# ProPrj_Line_follow_3_2025-06-26.net
KiCad netlist of a schematic drawn in EasyEDA Pro
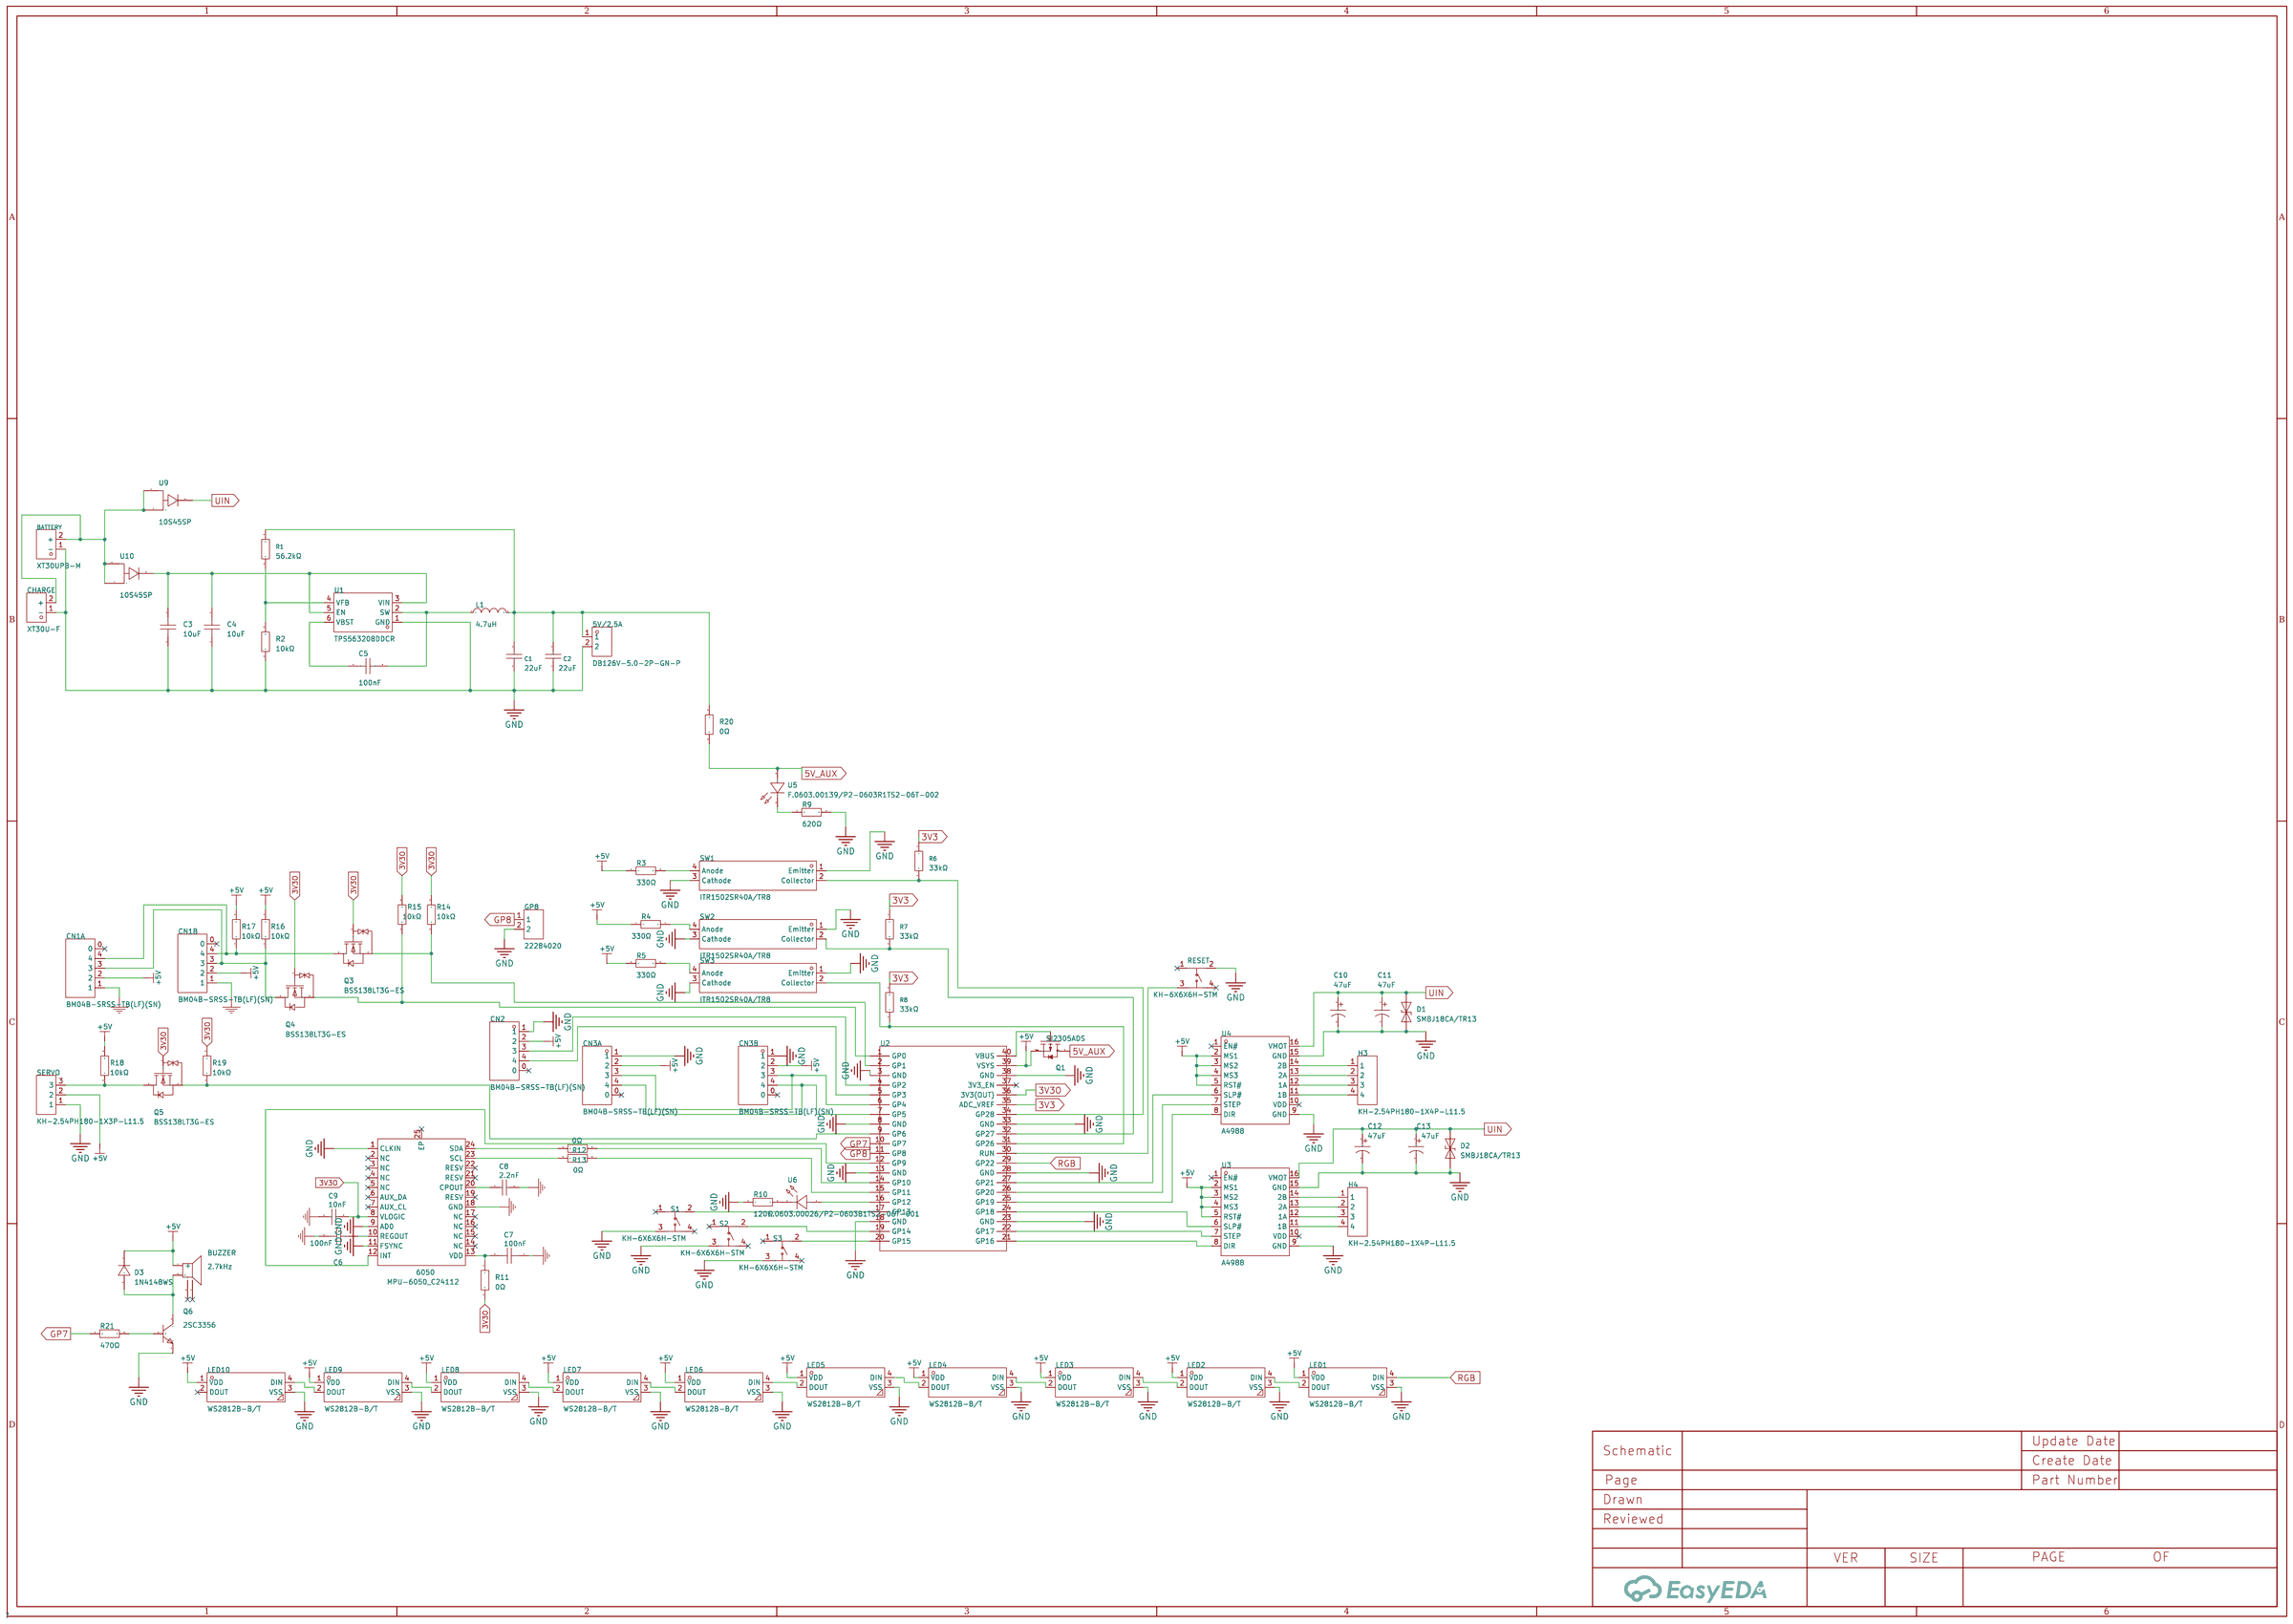
[diagram p0: schematic sheet]

(export (version "E")
  (design (tool "Eeschema 10.0.6"))
  (components
    (comp (ref "5V/2.5A")
      (value "DB126V-5.0-2P-GN-P")
      (footprint "easyedapro:CONN-TH_2P-P5.00_L7.8-W10.0")
      (fields (field (name "Manufacturer") "DORABO(地博电气)"))
      (libsource (lib "easyedapro") (part "DB126V-5.0-2P"))
    )
    (comp (ref "6050")
      (value "MPU-6050_C24112")
      (footprint "easyedapro:QFN-24_L4.0-W4.0-P0.50-BL-EP2.7")
      (fields
        (field (name "Manufacturer Part") "MPU-6050")
        (field (name "Manufacturer") "TDK InvenSense(应美盛)")
      )
      (libsource (lib "easyedapro") (part "MPU-6050_C24112"))
    )
    (comp (ref "BATTERY")
      (value "XT30UPB-M")
      (footprint "easyedapro:CONN-TH_XT30UPB-M")
      (fields (field (name "Manufacturer") "AMASS(艾迈斯)"))
      (libsource (lib "easyedapro") (part "XT30UPB-M"))
    )
    (comp (ref "BUZZER")
      (value "2.7kHz")
      (footprint "easyedapro:BUZ-SMD_4P-L8.5-W8.5-P8.50-BR")
      (fields (field (name "Manufacturer Part") "MLT-8530") (field (name "Manufacturer") "华能"))
      (libsource (lib "easyedapro") (part "MLT-8530"))
    )
    (comp (ref "C1")
      (value "22uF")
      (footprint "easyedapro:C1210")
      (fields
        (field (name "Manufacturer Part") "GRM32ER61E226KE15L")
        (field (name "Manufacturer") "muRata(村田)")
      )
      (libsource (lib "easyedapro") (part "GRM32ER61E226KE15L"))
    )
    (comp (ref "C2")
      (value "22uF")
      (footprint "easyedapro:C1210")
      (fields
        (field (name "Manufacturer Part") "GRM32ER61E226KE15L")
        (field (name "Manufacturer") "muRata(村田)")
      )
      (libsource (lib "easyedapro") (part "GRM32ER61E226KE15L"))
    )
    (comp (ref "C3")
      (value "10uF")
      (footprint "easyedapro:C1206")
      (fields
        (field (name "Manufacturer Part") "GRM31CR61E106KA12L")
        (field (name "Manufacturer") "muRata(村田)")
      )
      (libsource (lib "easyedapro") (part "GRM31CR61E106KA12L"))
    )
    (comp (ref "C4")
      (value "10uF")
      (footprint "easyedapro:C1206")
      (fields
        (field (name "Manufacturer Part") "GRM31CR61E106KA12L")
        (field (name "Manufacturer") "muRata(村田)")
      )
      (libsource (lib "easyedapro") (part "GRM31CR61E106KA12L"))
    )
    (comp (ref "C5")
      (value "100nF")
      (footprint "easyedapro:C0603")
      (fields
        (field (name "Manufacturer Part") "GRM188R71H104KA93D")
        (field (name "Manufacturer") "muRata(村田)")
      )
      (libsource (lib "easyedapro") (part "GRM188R71H104KA93D"))
    )
    (comp (ref "C6")
      (value "100nF")
      (footprint "easyedapro:C0603")
      (fields
        (field (name "Manufacturer Part") "CL10B104KB8NNNC")
        (field (name "Manufacturer") "SAMSUNG(三星)")
      )
      (libsource (lib "easyedapro") (part "100nF"))
    )
    (comp (ref "C7")
      (value "100nF")
      (footprint "easyedapro:C0603")
      (fields
        (field (name "Manufacturer Part") "CL10B104KB8NNNC")
        (field (name "Manufacturer") "SAMSUNG(三星)")
      )
      (libsource (lib "easyedapro") (part "100nF"))
    )
    (comp (ref "C8")
      (value "2.2nF")
      (footprint "easyedapro:C0603")
      (fields (field (name "Manufacturer Part") "0603B222K500NT") (field (name "Manufacturer") "FH(风华)"))
      (libsource (lib "easyedapro") (part "2.2nF"))
    )
    (comp (ref "C9")
      (value "10nF")
      (footprint "easyedapro:C0603")
      (fields
        (field (name "Manufacturer Part") "CL10B103KB8NNNC")
        (field (name "Manufacturer") "SAMSUNG(三星)")
      )
      (libsource (lib "easyedapro") (part "10nF"))
    )
    (comp (ref "C10")
      (value "47uF")
      (footprint "easyedapro:CAP-TH_BD6.3-P2.50-D1.0-FD")
      (fields
        (field (name "Manufacturer Part") "SPZ1HM470E08O00RAXXX")
        (field (name "Manufacturer") "AISHI(艾华集团)")
      )
      (libsource (lib "easyedapro") (part "SPZ1HM470E08000R"))
    )
    (comp (ref "C11")
      (value "47uF")
      (footprint "easyedapro:CAP-TH_BD6.3-P2.50-D1.0-FD")
      (fields
        (field (name "Manufacturer Part") "SPZ1HM470E08O00RAXXX")
        (field (name "Manufacturer") "AISHI(艾华集团)")
      )
      (libsource (lib "easyedapro") (part "SPZ1HM470E08000R"))
    )
    (comp (ref "C12")
      (value "47uF")
      (footprint "easyedapro:CAP-TH_BD6.3-P2.50-D1.0-FD")
      (fields
        (field (name "Manufacturer Part") "SPZ1HM470E08O00RAXXX")
        (field (name "Manufacturer") "AISHI(艾华集团)")
      )
      (libsource (lib "easyedapro") (part "SPZ1HM470E08000R"))
    )
    (comp (ref "C13")
      (value "47uF")
      (footprint "easyedapro:CAP-TH_BD6.3-P2.50-D1.0-FD")
      (fields
        (field (name "Manufacturer Part") "SPZ1HM470E08O00RAXXX")
        (field (name "Manufacturer") "AISHI(艾华集团)")
      )
      (libsource (lib "easyedapro") (part "SPZ1HM470E08000R"))
    )
    (comp (ref "CHARGE")
      (value "XT30U-F")
      (footprint "easyedapro:CONN-TH_XT30U-F")
      (fields (field (name "Manufacturer") "AMASS(艾迈斯)"))
      (libsource (lib "easyedapro") (part "XT30U-F"))
    )
    (comp (ref "CN1A")
      (value "BM04B-SRSS-TB(LF)(SN)")
      (footprint "easyedapro:CONN-SMD_BM04B-SRSS-TB")
      (fields (field (name "Manufacturer") "JST"))
      (libsource (lib "") (part "BM04B-SRSS-TB(LF)(SN)_1"))
    )
    (comp (ref "CN1B")
      (value "BM04B-SRSS-TB(LF)(SN)")
      (footprint "easyedapro:CONN-SMD_BM04B-SRSS-TB")
      (fields (field (name "Manufacturer") "JST"))
      (libsource (lib "") (part "BM04B-SRSS-TB(LF)(SN)_1"))
    )
    (comp (ref "CN2")
      (value "BM04B-SRSS-TB(LF)(SN)")
      (footprint "easyedapro:CONN-SMD_BM04B-SRSS-TB")
      (fields (field (name "Manufacturer") "JST"))
      (libsource (lib "easyedapro") (part "BM04B-SRSS-TB(LF)(SN)"))
    )
    (comp (ref "CN3A")
      (value "BM04B-SRSS-TB(LF)(SN)")
      (footprint "easyedapro:CONN-SMD_BM04B-SRSS-TB")
      (fields (field (name "Manufacturer") "JST"))
      (libsource (lib "easyedapro") (part "BM04B-SRSS-TB(LF)(SN)"))
    )
    (comp (ref "CN3B")
      (value "BM04B-SRSS-TB(LF)(SN)")
      (footprint "easyedapro:CONN-SMD_BM04B-SRSS-TB")
      (fields (field (name "Manufacturer") "JST"))
      (libsource (lib "easyedapro") (part "BM04B-SRSS-TB(LF)(SN)"))
    )
    (comp (ref "D1")
      (value "SMBJ18CA/TR13")
      (footprint "easyedapro:SMB_L4.6-W3.6-LS5.3-BI")
      (fields (field (name "Manufacturer") "Brightking(君耀电子)"))
      (libsource (lib "easyedapro") (part "SMBJ18CA-C78413"))
    )
    (comp (ref "D2")
      (value "SMBJ18CA/TR13")
      (footprint "easyedapro:SMB_L4.6-W3.6-LS5.3-BI")
      (fields (field (name "Manufacturer") "Brightking(君耀电子)"))
      (libsource (lib "easyedapro") (part "SMBJ18CA-C78413"))
    )
    (comp (ref "D3")
      (value "1N4148WS")
      (footprint "easyedapro:SOD-323_L1.8-W1.3-LS2.5-RD")
      (fields (field (name "Manufacturer") "CJ(江苏长电/长晶)"))
      (libsource (lib "easyedapro") (part "1N4148WS T4"))
    )
    (comp (ref "GP8")
      (value "22284020")
      (footprint "easyedapro:HDR-TH_2P-P2.54-V-M-1")
      (fields (field (name "Manufacturer") "MOLEX"))
      (libsource (lib "easyedapro") (part "22-28-4020"))
    )
    (comp (ref "H3")
      (value "KH-2.54PH180-1X4P-L11.5")
      (footprint "easyedapro:HDR-TH_4P-P2.54-V-M")
      (fields (field (name "Manufacturer") "kinghelm(金航标)"))
      (libsource (lib "easyedapro") (part "KH-2.54PH180-1X4P-L11.5"))
    )
    (comp (ref "H4")
      (value "KH-2.54PH180-1X4P-L11.5")
      (footprint "easyedapro:HDR-TH_4P-P2.54-V-M")
      (fields (field (name "Manufacturer") "kinghelm(金航标)"))
      (libsource (lib "easyedapro") (part "KH-2.54PH180-1X4P-L11.5"))
    )
    (comp (ref "L1")
      (value "4.7uH")
      (footprint "easyedapro:IND-SMD_L7.0-W6.6")
      (fields (field (name "Manufacturer Part") "FXL0630-4R7-M") (field (name "Manufacturer") "cjiang(长江微电)"))
      (libsource (lib "easyedapro") (part "FXL0630-4R7-M"))
    )
    (comp (ref "LED1")
      (value "WS2812B-B/T")
      (footprint "easyedapro:LED-SMD_4P-L5.0-W5.0-TL_WS2812B-B")
      (fields (field (name "Manufacturer") "worldsemi"))
      (libsource (lib "easyedapro") (part "WS2812B-B/W"))
    )
    (comp (ref "LED2")
      (value "WS2812B-B/T")
      (footprint "easyedapro:LED-SMD_4P-L5.0-W5.0-TL_WS2812B-B")
      (fields (field (name "Manufacturer") "worldsemi"))
      (libsource (lib "easyedapro") (part "WS2812B-B/W"))
    )
    (comp (ref "LED3")
      (value "WS2812B-B/T")
      (footprint "easyedapro:LED-SMD_4P-L5.0-W5.0-TL_WS2812B-B")
      (fields (field (name "Manufacturer") "worldsemi"))
      (libsource (lib "easyedapro") (part "WS2812B-B/W"))
    )
    (comp (ref "LED4")
      (value "WS2812B-B/T")
      (footprint "easyedapro:LED-SMD_4P-L5.0-W5.0-TL_WS2812B-B")
      (fields (field (name "Manufacturer") "worldsemi"))
      (libsource (lib "easyedapro") (part "WS2812B-B/W"))
    )
    (comp (ref "LED5")
      (value "WS2812B-B/T")
      (footprint "easyedapro:LED-SMD_4P-L5.0-W5.0-TL_WS2812B-B")
      (fields (field (name "Manufacturer") "worldsemi"))
      (libsource (lib "easyedapro") (part "WS2812B-B/W"))
    )
    (comp (ref "LED6")
      (value "WS2812B-B/T")
      (footprint "easyedapro:LED-SMD_4P-L5.0-W5.0-TL_WS2812B-B")
      (fields (field (name "Manufacturer") "worldsemi"))
      (libsource (lib "easyedapro") (part "WS2812B-B/W"))
    )
    (comp (ref "LED7")
      (value "WS2812B-B/T")
      (footprint "easyedapro:LED-SMD_4P-L5.0-W5.0-TL_WS2812B-B")
      (fields (field (name "Manufacturer") "worldsemi"))
      (libsource (lib "easyedapro") (part "WS2812B-B/W"))
    )
    (comp (ref "LED8")
      (value "WS2812B-B/T")
      (footprint "easyedapro:LED-SMD_4P-L5.0-W5.0-TL_WS2812B-B")
      (fields (field (name "Manufacturer") "worldsemi"))
      (libsource (lib "easyedapro") (part "WS2812B-B/W"))
    )
    (comp (ref "LED9")
      (value "WS2812B-B/T")
      (footprint "easyedapro:LED-SMD_4P-L5.0-W5.0-TL_WS2812B-B")
      (fields (field (name "Manufacturer") "worldsemi"))
      (libsource (lib "easyedapro") (part "WS2812B-B/W"))
    )
    (comp (ref "LED10")
      (value "WS2812B-B/T")
      (footprint "easyedapro:LED-SMD_4P-L5.0-W5.0-TL_WS2812B-B")
      (fields (field (name "Manufacturer") "worldsemi"))
      (libsource (lib "easyedapro") (part "WS2812B-B/W"))
    )
    (comp (ref "Q1")
      (value "SI2305ADS")
      (footprint "easyedapro:SOT-23-3_L2.9-W1.3-P1.90-LS2.4-BR")
      (fields (field (name "Manufacturer") "TECH PUBLIC(台舟)"))
      (libsource (lib "easyedapro") (part "SI2305ADS"))
    )
    (comp (ref "Q3")
      (value "BSS138LT3G-ES")
      (footprint "easyedapro:SOT-23-3_L2.9-W1.3-P1.90-LS2.4-BR")
      (fields (field (name "Manufacturer") "ElecSuper(静芯微)"))
      (libsource (lib "easyedapro") (part "BSS138LT3G-ES"))
    )
    (comp (ref "Q4")
      (value "BSS138LT3G-ES")
      (footprint "easyedapro:SOT-23-3_L2.9-W1.3-P1.90-LS2.4-BR")
      (fields (field (name "Manufacturer") "ElecSuper(静芯微)"))
      (libsource (lib "easyedapro") (part "BSS138LT3G-ES"))
    )
    (comp (ref "Q5")
      (value "BSS138LT3G-ES")
      (footprint "easyedapro:SOT-23-3_L2.9-W1.3-P1.90-LS2.4-BR")
      (fields (field (name "Manufacturer") "ElecSuper(静芯微)"))
      (libsource (lib "easyedapro") (part "BSS138LT3G-ES"))
    )
    (comp (ref "Q6")
      (value "2SC3356")
      (footprint "easyedapro:SOT-23-3_L2.9-W1.3-P1.90-LS2.4-BR")
      (fields (field (name "Manufacturer") "宏嘉诚"))
      (libsource (lib "easyedapro") (part "2SC3356_C28646266"))
    )
    (comp (ref "R1")
      (value "56.2kΩ")
      (footprint "easyedapro:R0402")
      (fields
        (field (name "Manufacturer Part") "0402WGF5622TCE")
        (field (name "Manufacturer") "UNI-ROYAL(厚声)")
      )
      (libsource (lib "easyedapro") (part "0402WGF5622TCE"))
    )
    (comp (ref "R2")
      (value "10kΩ")
      (footprint "easyedapro:R0402")
      (fields
        (field (name "Manufacturer Part") "0402WGF1002TCE")
        (field (name "Manufacturer") "UNI-ROYAL(厚声)")
      )
      (libsource (lib "easyedapro") (part "0402WGF1002TCE"))
    )
    (comp (ref "R3")
      (value "330Ω")
      (footprint "easyedapro:R0603")
      (fields
        (field (name "Manufacturer Part") "0603WAF3300T5E")
        (field (name "Manufacturer") "UNI-ROYAL(厚声)")
      )
      (libsource (lib "easyedapro") (part "0603WAF3300T5E"))
    )
    (comp (ref "R4")
      (value "330Ω")
      (footprint "easyedapro:R0603")
      (fields
        (field (name "Manufacturer Part") "0603WAF3300T5E")
        (field (name "Manufacturer") "UNI-ROYAL(厚声)")
      )
      (libsource (lib "easyedapro") (part "0603WAF3300T5E"))
    )
    (comp (ref "R5")
      (value "330Ω")
      (footprint "easyedapro:R0603")
      (fields
        (field (name "Manufacturer Part") "0603WAF3300T5E")
        (field (name "Manufacturer") "UNI-ROYAL(厚声)")
      )
      (libsource (lib "easyedapro") (part "0603WAF3300T5E"))
    )
    (comp (ref "R6")
      (value "33kΩ")
      (footprint "easyedapro:R0603")
      (fields
        (field (name "Manufacturer Part") "0603WAF3302T5E")
        (field (name "Manufacturer") "UNI-ROYAL(厚声)")
      )
      (libsource (lib "easyedapro") (part "0603WAF3302T5E"))
    )
    (comp (ref "R7")
      (value "33kΩ")
      (footprint "easyedapro:R0603")
      (fields
        (field (name "Manufacturer Part") "0603WAF3302T5E")
        (field (name "Manufacturer") "UNI-ROYAL(厚声)")
      )
      (libsource (lib "easyedapro") (part "0603WAF3302T5E"))
    )
    (comp (ref "R8")
      (value "33kΩ")
      (footprint "easyedapro:R0603")
      (fields
        (field (name "Manufacturer Part") "0603WAF3302T5E")
        (field (name "Manufacturer") "UNI-ROYAL(厚声)")
      )
      (libsource (lib "easyedapro") (part "0603WAF3302T5E"))
    )
    (comp (ref "R9")
      (value "620Ω")
      (footprint "easyedapro:R0603")
      (fields (field (name "Manufacturer Part") "RC0603FR-07620RL") (field (name "Manufacturer") "YAGEO(国巨)"))
      (libsource (lib "easyedapro") (part "RC0603FR-07620RL"))
    )
    (comp (ref "R10")
      (value "120Ω")
      (footprint "easyedapro:R0603")
      (fields (field (name "Manufacturer Part") "RC0603FR-07120RL") (field (name "Manufacturer") "YAGEO(国巨)"))
      (libsource (lib "easyedapro") (part "RC0603FR-07120RL"))
    )
    (comp (ref "R11")
      (value "0Ω")
      (footprint "easyedapro:R0603")
      (fields
        (field (name "Manufacturer Part") "0603WAJ0000T5E")
        (field (name "Manufacturer") "UNI-ROYAL(厚声)")
      )
      (libsource (lib "easyedapro") (part "0Ω"))
    )
    (comp (ref "R12")
      (value "0Ω")
      (footprint "easyedapro:R0603")
      (fields
        (field (name "Manufacturer Part") "0603WAJ0000T5E")
        (field (name "Manufacturer") "UNI-ROYAL(厚声)")
      )
      (libsource (lib "easyedapro") (part "0Ω"))
    )
    (comp (ref "R13")
      (value "0Ω")
      (footprint "easyedapro:R0603")
      (fields
        (field (name "Manufacturer Part") "0603WAJ0000T5E")
        (field (name "Manufacturer") "UNI-ROYAL(厚声)")
      )
      (libsource (lib "easyedapro") (part "0Ω"))
    )
    (comp (ref "R14")
      (value "10kΩ")
      (footprint "easyedapro:R0603")
      (fields (field (name "Manufacturer Part") "AC0603FR-0710KL") (field (name "Manufacturer") "YAGEO(国巨)"))
      (libsource (lib "easyedapro") (part "10kΩ"))
    )
    (comp (ref "R15")
      (value "10kΩ")
      (footprint "easyedapro:R0603")
      (fields (field (name "Manufacturer Part") "AC0603FR-0710KL") (field (name "Manufacturer") "YAGEO(国巨)"))
      (libsource (lib "easyedapro") (part "10kΩ"))
    )
    (comp (ref "R16")
      (value "10kΩ")
      (footprint "easyedapro:R0603")
      (fields (field (name "Manufacturer Part") "AC0603FR-0710KL") (field (name "Manufacturer") "YAGEO(国巨)"))
      (libsource (lib "easyedapro") (part "10kΩ"))
    )
    (comp (ref "R17")
      (value "10kΩ")
      (footprint "easyedapro:R0603")
      (fields (field (name "Manufacturer Part") "AC0603FR-0710KL") (field (name "Manufacturer") "YAGEO(国巨)"))
      (libsource (lib "easyedapro") (part "10kΩ"))
    )
    (comp (ref "R18")
      (value "10kΩ")
      (footprint "easyedapro:R0603")
      (fields (field (name "Manufacturer Part") "AC0603FR-0710KL") (field (name "Manufacturer") "YAGEO(国巨)"))
      (libsource (lib "easyedapro") (part "10kΩ"))
    )
    (comp (ref "R19")
      (value "10kΩ")
      (footprint "easyedapro:R0603")
      (fields (field (name "Manufacturer Part") "AC0603FR-0710KL") (field (name "Manufacturer") "YAGEO(国巨)"))
      (libsource (lib "easyedapro") (part "10kΩ"))
    )
    (comp (ref "R20")
      (value "0Ω")
      (footprint "easyedapro:R0603")
      (fields
        (field (name "Manufacturer Part") "0603WAJ0000T5E")
        (field (name "Manufacturer") "UNI-ROYAL(厚声)")
      )
      (libsource (lib "easyedapro") (part "0Ω"))
    )
    (comp (ref "R21")
      (value "470Ω")
      (footprint "easyedapro:R0603")
      (fields
        (field (name "Manufacturer Part") "0603WAF4700T5E")
        (field (name "Manufacturer") "UNI-ROYAL(厚声)")
      )
      (libsource (lib "easyedapro") (part "0603WAF4700T5E"))
    )
    (comp (ref "RESET")
      (value "KH-6X6X6H-STM")
      (footprint "easyedapro:SW-SMD_4P-L6.0-W6.0-P4.50-LS9.0-3")
      (fields (field (name "Manufacturer") "kinghelm(金航标)"))
      (libsource (lib "easyedapro") (part "KH-6X6X6H-STM"))
    )
    (comp (ref "S1")
      (value "KH-6X6X6H-STM")
      (footprint "easyedapro:SW-SMD_4P-L6.0-W6.0-P4.50-LS9.0-3")
      (fields (field (name "Manufacturer") "kinghelm(金航标)"))
      (libsource (lib "easyedapro") (part "KH-6X6X6H-STM"))
    )
    (comp (ref "S2")
      (value "KH-6X6X6H-STM")
      (footprint "easyedapro:SW-SMD_4P-L6.0-W6.0-P4.50-LS9.0-3")
      (fields (field (name "Manufacturer") "kinghelm(金航标)"))
      (libsource (lib "easyedapro") (part "KH-6X6X6H-STM"))
    )
    (comp (ref "S3")
      (value "KH-6X6X6H-STM")
      (footprint "easyedapro:SW-SMD_4P-L6.0-W6.0-P4.50-LS9.0-3")
      (fields (field (name "Manufacturer") "kinghelm(金航标)"))
      (libsource (lib "easyedapro") (part "KH-6X6X6H-STM"))
    )
    (comp (ref "SERVO")
      (value "KH-2.54PH180-1X3P-L11.5")
      (footprint "easyedapro:HDR-TH_3P-P2.54-V-M")
      (fields (field (name "Manufacturer") "kinghelm(金航标)"))
      (libsource (lib "easyedapro") (part "KH-2.54PH180-1X3P-L11.5"))
    )
    (comp (ref "SW1")
      (value "ITR1502SR40A/TR8")
      (footprint "easyedapro:SW-SMD_4P-L4.0-W3.0_ITR1502SR40A-TR8")
      (fields (field (name "Manufacturer") "EVERLIGHT(亿光)"))
      (libsource (lib "easyedapro") (part "ITR1502SR40A/TR8"))
    )
    (comp (ref "SW2")
      (value "ITR1502SR40A/TR8")
      (footprint "easyedapro:SW-SMD_4P-L4.0-W3.0_ITR1502SR40A-TR8")
      (fields (field (name "Manufacturer") "EVERLIGHT(亿光)"))
      (libsource (lib "easyedapro") (part "ITR1502SR40A/TR8"))
    )
    (comp (ref "SW3")
      (value "ITR1502SR40A/TR8")
      (footprint "easyedapro:SW-SMD_4P-L4.0-W3.0_ITR1502SR40A-TR8")
      (fields (field (name "Manufacturer") "EVERLIGHT(亿光)"))
      (libsource (lib "easyedapro") (part "ITR1502SR40A/TR8"))
    )
    (comp (ref "U1")
      (value "TPS563208DDCR")
      (footprint "easyedapro:TSOT-23-6_L2.9-W1.6-P0.95-LS2.8-BL")
      (fields (field (name "Manufacturer") "TI(德州仪器)"))
      (libsource (lib "easyedapro") (part "TPS563208DDCR"))
    )
    (comp (ref "U2")
      (value "~")
      (footprint "easyedapro:RPI_PICO_DIL")
      (description "Raspberry pi pico in DIL")
      (libsource (lib "easyedapro") (part "RPI_PICO_DIL"))
    )
    (comp (ref "U3")
      (value "A4988")
      (footprint "easyedapro:DIP-16_L20.3-W15.2-P2.54_LS12.7_A4988")
      (libsource (lib "easyedapro") (part "A4988"))
    )
    (comp (ref "U4")
      (value "A4988")
      (footprint "easyedapro:DIP-16_L20.3-W15.2-P2.54_LS12.7_A4988")
      (libsource (lib "easyedapro") (part "A4988"))
    )
    (comp (ref "U5")
      (value "F.0603.00139/P2-0603R1TS2-06T-002")
      (footprint "easyedapro:LED0603-RD")
      (fields (field (name "Manufacturer") "TUOZHAN(拓展光电)"))
      (libsource (lib "easyedapro") (part "F.0603.00139/P2-0603R1TS2-06T-002"))
    )
    (comp (ref "U6")
      (value "F.0603.00026/P2-0603B1TS2-06T-001")
      (footprint "easyedapro:LED0603-RD")
      (fields (field (name "Manufacturer") "TUOZHAN(拓展光电)"))
      (libsource (lib "easyedapro") (part "F.0603.00026/P2-0603B1TS2-06T-001"))
    )
    (comp (ref "U9")
      (value "10S45SP")
      (footprint "easyedapro:TO-277_3P-L5.4-W4.0-LS6.5-TR-1")
      (fields (field (name "Manufacturer") "YFW(佑风微)"))
      (libsource (lib "easyedapro") (part "10S45SP"))
    )
    (comp (ref "U10")
      (value "10S45SP")
      (footprint "easyedapro:TO-277_3P-L5.4-W4.0-LS6.5-TR-1")
      (fields (field (name "Manufacturer") "YFW(佑风微)"))
      (libsource (lib "easyedapro") (part "10S45SP"))
    )
  )
  (nets
    (net (code "1") (name "+5V") (class "Default")
      (node (ref "BUZZER") (pin "1") (pinfunction "+_1") (pintype "unspecified"))
      (node (ref "CN1A") (pin "2") (pinfunction "2_2") (pintype "unspecified"))
      (node (ref "CN1B") (pin "2") (pinfunction "2_2") (pintype "unspecified"))
      (node (ref "CN2") (pin "2") (pinfunction "2_2") (pintype "unspecified"))
      (node (ref "CN3A") (pin "2") (pinfunction "2_2") (pintype "unspecified"))
      (node (ref "CN3B") (pin "2") (pinfunction "2_2") (pintype "unspecified"))
      (node (ref "D3") (pin "1") (pinfunction "K_1") (pintype "unspecified"))
      (node (ref "LED1") (pin "1") (pinfunction "VDD_1") (pintype "unspecified"))
      (node (ref "LED10") (pin "1") (pinfunction "VDD_1") (pintype "unspecified"))
      (node (ref "LED2") (pin "1") (pinfunction "VDD_1") (pintype "unspecified"))
      (node (ref "LED3") (pin "1") (pinfunction "VDD_1") (pintype "unspecified"))
      (node (ref "LED4") (pin "1") (pinfunction "VDD_1") (pintype "unspecified"))
      (node (ref "LED5") (pin "1") (pinfunction "VDD_1") (pintype "unspecified"))
      (node (ref "LED6") (pin "1") (pinfunction "VDD_1") (pintype "unspecified"))
      (node (ref "LED7") (pin "1") (pinfunction "VDD_1") (pintype "unspecified"))
      (node (ref "LED8") (pin "1") (pinfunction "VDD_1") (pintype "unspecified"))
      (node (ref "LED9") (pin "1") (pinfunction "VDD_1") (pintype "unspecified"))
      (node (ref "Q1") (pin "2") (pinfunction "S_2") (pintype "unspecified"))
      (node (ref "R16") (pin "2") (pinfunction "2_2") (pintype "input"))
      (node (ref "R17") (pin "2") (pinfunction "2_2") (pintype "input"))
      (node (ref "R18") (pin "2") (pinfunction "2_2") (pintype "input"))
      (node (ref "R3") (pin "1") (pinfunction "1_1") (pintype "input"))
      (node (ref "R4") (pin "1") (pinfunction "1_1") (pintype "input"))
      (node (ref "R5") (pin "1") (pinfunction "1_1") (pintype "input"))
      (node (ref "SERVO") (pin "2") (pinfunction "2_2") (pintype "unspecified"))
      (node (ref "U2") (pin "39") (pinfunction "VSYS_39") (pintype "input"))
      (node (ref "U3") (pin "2") (pinfunction "MS1_2") (pintype "unspecified"))
      (node (ref "U3") (pin "3") (pinfunction "MS2_3") (pintype "unspecified"))
      (node (ref "U3") (pin "4") (pinfunction "MS3_4") (pintype "unspecified"))
      (node (ref "U3") (pin "5") (pinfunction "RST#_5") (pintype "unspecified"))
      (node (ref "U4") (pin "2") (pinfunction "MS1_2") (pintype "unspecified"))
      (node (ref "U4") (pin "3") (pinfunction "MS2_3") (pintype "unspecified"))
      (node (ref "U4") (pin "4") (pinfunction "MS3_4") (pintype "unspecified"))
      (node (ref "U4") (pin "5") (pinfunction "RST#_5") (pintype "unspecified"))
    )
    (net (code "2") (name "3V3") (class "Default")
      (node (ref "R6") (pin "1") (pinfunction "1_1") (pintype "input"))
      (node (ref "R7") (pin "1") (pinfunction "1_1") (pintype "input"))
      (node (ref "R8") (pin "2") (pinfunction "2_2") (pintype "input"))
      (node (ref "U2") (pin "35") (pinfunction "ADC_VREF_35") (pintype "input"))
    )
    (net (code "3") (name "3V3O") (class "Default")
      (node (ref "6050") (pin "8") (pinfunction "VLOGIC_8") (pintype "unspecified"))
      (node (ref "C9") (pin "2") (pinfunction "2_2") (pintype "input"))
      (node (ref "Q3") (pin "1") (pinfunction "G_1") (pintype "unspecified"))
      (node (ref "Q4") (pin "1") (pinfunction "G_1") (pintype "unspecified"))
      (node (ref "Q5") (pin "1") (pinfunction "G_1") (pintype "unspecified"))
      (node (ref "R11") (pin "2") (pinfunction "2_2") (pintype "input"))
      (node (ref "R14") (pin "2") (pinfunction "2_2") (pintype "input"))
      (node (ref "R15") (pin "2") (pinfunction "2_2") (pintype "input"))
      (node (ref "R19") (pin "2") (pinfunction "2_2") (pintype "input"))
      (node (ref "U2") (pin "36") (pinfunction "3V3(OUT)_36") (pintype "input"))
    )
    (net (code "4") (name "5V_AUX") (class "Default")
      (node (ref "Q1") (pin "3") (pinfunction "D_3") (pintype "unspecified"))
      (node (ref "R20") (pin "2") (pinfunction "2_2") (pintype "input"))
      (node (ref "U5") (pin "2") (pinfunction "A_2") (pintype "unspecified"))
    )
    (net (code "5") (name "GND") (class "Default")
      (node (ref "5V/2.5A") (pin "2") (pinfunction "2_2") (pintype "unspecified"))
      (node (ref "6050") (pin "1") (pinfunction "CLKIN_1") (pintype "unspecified"))
      (node (ref "6050") (pin "11") (pinfunction "FSYNC_11") (pintype "unspecified"))
      (node (ref "6050") (pin "18") (pinfunction "GND_18") (pintype "unspecified"))
      (node (ref "6050") (pin "9") (pinfunction "AD0_9") (pintype "unspecified"))
      (node (ref "BATTERY") (pin "1") (pinfunction "-_1") (pintype "input"))
      (node (ref "C1") (pin "2") (pinfunction "2_2") (pintype "input"))
      (node (ref "C10") (pin "2") (pinfunction "2_2") (pintype "input"))
      (node (ref "C11") (pin "2") (pinfunction "2_2") (pintype "input"))
      (node (ref "C12") (pin "2") (pinfunction "2_2") (pintype "input"))
      (node (ref "C13") (pin "2") (pinfunction "2_2") (pintype "input"))
      (node (ref "C2") (pin "1") (pinfunction "1_1") (pintype "input"))
      (node (ref "C3") (pin "1") (pinfunction "1_1") (pintype "unspecified"))
      (node (ref "C4") (pin "1") (pinfunction "1_1") (pintype "unspecified"))
      (node (ref "C6") (pin "2") (pinfunction "2_2") (pintype "unspecified"))
      (node (ref "C7") (pin "1") (pinfunction "1_1") (pintype "unspecified"))
      (node (ref "C8") (pin "2") (pinfunction "2_2") (pintype "input"))
      (node (ref "C9") (pin "1") (pinfunction "1_1") (pintype "input"))
      (node (ref "CHARGE") (pin "1") (pinfunction "-_1") (pintype "unspecified"))
      (node (ref "CN1A") (pin "1") (pinfunction "1_1") (pintype "unspecified"))
      (node (ref "CN1B") (pin "1") (pinfunction "1_1") (pintype "unspecified"))
      (node (ref "CN2") (pin "1") (pinfunction "1_1") (pintype "unspecified"))
      (node (ref "CN3A") (pin "1") (pinfunction "1_1") (pintype "unspecified"))
      (node (ref "CN3B") (pin "1") (pinfunction "1_1") (pintype "unspecified"))
      (node (ref "D1") (pin "2") (pinfunction "2_2") (pintype "unspecified"))
      (node (ref "D2") (pin "1") (pinfunction "1_1") (pintype "unspecified"))
      (node (ref "GP8") (pin "2") (pinfunction "2_2") (pintype "unspecified"))
      (node (ref "LED1") (pin "3") (pinfunction "VSS_3") (pintype "unspecified"))
      (node (ref "LED10") (pin "3") (pinfunction "VSS_3") (pintype "unspecified"))
      (node (ref "LED2") (pin "3") (pinfunction "VSS_3") (pintype "unspecified"))
      (node (ref "LED3") (pin "3") (pinfunction "VSS_3") (pintype "unspecified"))
      (node (ref "LED4") (pin "3") (pinfunction "VSS_3") (pintype "unspecified"))
      (node (ref "LED5") (pin "3") (pinfunction "VSS_3") (pintype "unspecified"))
      (node (ref "LED6") (pin "3") (pinfunction "VSS_3") (pintype "unspecified"))
      (node (ref "LED7") (pin "3") (pinfunction "VSS_3") (pintype "unspecified"))
      (node (ref "LED8") (pin "3") (pinfunction "VSS_3") (pintype "unspecified"))
      (node (ref "LED9") (pin "3") (pinfunction "VSS_3") (pintype "unspecified"))
      (node (ref "Q6") (pin "2") (pinfunction "E_2") (pintype "input"))
      (node (ref "R10") (pin "1") (pinfunction "1_1") (pintype "input"))
      (node (ref "R2") (pin "1") (pinfunction "1_1") (pintype "input"))
      (node (ref "R9") (pin "2") (pinfunction "2_2") (pintype "input"))
      (node (ref "RESET") (pin "2") (pinfunction "B_2") (pintype "unspecified"))
      (node (ref "S1") (pin "3") (pinfunction "C_3") (pintype "unspecified"))
      (node (ref "S2") (pin "3") (pinfunction "C_3") (pintype "unspecified"))
      (node (ref "S3") (pin "3") (pinfunction "C_3") (pintype "unspecified"))
      (node (ref "SERVO") (pin "1") (pinfunction "1_1") (pintype "unspecified"))
      (node (ref "SW1") (pin "1") (pinfunction "Emitter_1") (pintype "unspecified"))
      (node (ref "SW1") (pin "3") (pinfunction "Cathode_3") (pintype "unspecified"))
      (node (ref "SW2") (pin "1") (pinfunction "Emitter_1") (pintype "unspecified"))
      (node (ref "SW2") (pin "3") (pinfunction "Cathode_3") (pintype "unspecified"))
      (node (ref "SW3") (pin "1") (pinfunction "Emitter_1") (pintype "unspecified"))
      (node (ref "SW3") (pin "3") (pinfunction "Cathode_3") (pintype "unspecified"))
      (node (ref "U1") (pin "1") (pinfunction "GND_1") (pintype "unspecified"))
      (node (ref "U2") (pin "13") (pinfunction "GND_13") (pintype "input"))
      (node (ref "U2") (pin "18") (pinfunction "GND_18") (pintype "input"))
      (node (ref "U2") (pin "23") (pinfunction "GND_23") (pintype "input"))
      (node (ref "U2") (pin "28") (pinfunction "GND_28") (pintype "input"))
      (node (ref "U2") (pin "3") (pinfunction "GND_3") (pintype "input"))
      (node (ref "U2") (pin "33") (pinfunction "GND_33") (pintype "input"))
      (node (ref "U2") (pin "38") (pinfunction "GND_38") (pintype "input"))
      (node (ref "U2") (pin "8") (pinfunction "GND_8") (pintype "input"))
      (node (ref "U3") (pin "15") (pinfunction "GND_15") (pintype "unspecified"))
      (node (ref "U3") (pin "9") (pinfunction "GND_9") (pintype "unspecified"))
      (node (ref "U4") (pin "15") (pinfunction "GND_15") (pintype "unspecified"))
      (node (ref "U4") (pin "9") (pinfunction "GND_9") (pintype "unspecified"))
    )
    (net (code "6") (name "GP7") (class "Default")
      (node (ref "R21") (pin "1") (pinfunction "1_1") (pintype "input"))
      (node (ref "U2") (pin "10") (pinfunction "GP7_10") (pintype "input"))
    )
    (net (code "7") (name "GP8") (class "Default")
      (node (ref "GP8") (pin "1") (pinfunction "1_1") (pintype "unspecified"))
      (node (ref "U2") (pin "11") (pinfunction "GP8_11") (pintype "input"))
    )
    (net (code "8") (name "Net-(5V/2.5A-Pad1)") (class "Default")
      (node (ref "5V/2.5A") (pin "1") (pinfunction "1_1") (pintype "unspecified"))
      (node (ref "C1") (pin "1") (pinfunction "1_1") (pintype "input"))
      (node (ref "C2") (pin "2") (pinfunction "2_2") (pintype "input"))
      (node (ref "L1") (pin "2") (pinfunction "2_2") (pintype "unspecified"))
      (node (ref "R1") (pin "2") (pinfunction "2_2") (pintype "input"))
      (node (ref "R20") (pin "1") (pinfunction "1_1") (pintype "input"))
    )
    (net (code "9") (name "Net-(6050-CPOUT)") (class "Default")
      (node (ref "6050") (pin "20") (pinfunction "CPOUT_20") (pintype "unspecified"))
      (node (ref "C8") (pin "1") (pinfunction "1_1") (pintype "input"))
    )
    (net (code "10") (name "Net-(6050-INT)") (class "Default")
      (node (ref "6050") (pin "12") (pinfunction "INT_12") (pintype "unspecified"))
      (node (ref "U2") (pin "12") (pinfunction "GP9_12") (pintype "input"))
    )
    (net (code "11") (name "Net-(6050-REGOUT)") (class "Default")
      (node (ref "6050") (pin "10") (pinfunction "REGOUT_10") (pintype "unspecified"))
      (node (ref "C6") (pin "1") (pinfunction "1_1") (pintype "unspecified"))
    )
    (net (code "12") (name "Net-(6050-SCL)") (class "Default")
      (node (ref "6050") (pin "23") (pinfunction "SCL_23") (pintype "unspecified"))
      (node (ref "R13") (pin "1") (pinfunction "1_1") (pintype "input"))
    )
    (net (code "13") (name "Net-(6050-SDA)") (class "Default")
      (node (ref "6050") (pin "24") (pinfunction "SDA_24") (pintype "unspecified"))
      (node (ref "R12") (pin "1") (pinfunction "1_1") (pintype "input"))
    )
    (net (code "14") (name "Net-(6050-VDD)") (class "Default")
      (node (ref "6050") (pin "13") (pinfunction "VDD_13") (pintype "unspecified"))
      (node (ref "C7") (pin "2") (pinfunction "2_2") (pintype "unspecified"))
      (node (ref "R11") (pin "1") (pinfunction "1_1") (pintype "input"))
    )
    (net (code "15") (name "Net-(BATTERY-+)") (class "Default")
      (node (ref "BATTERY") (pin "2") (pinfunction "+_2") (pintype "input"))
      (node (ref "CHARGE") (pin "2") (pinfunction "+_2") (pintype "unspecified"))
      (node (ref "U10") (pin "1") (pinfunction "A_1") (pintype "unspecified"))
      (node (ref "U10") (pin "2") (pinfunction "A_2") (pintype "unspecified"))
      (node (ref "U9") (pin "1") (pinfunction "A_1") (pintype "unspecified"))
      (node (ref "U9") (pin "2") (pinfunction "A_2") (pintype "unspecified"))
    )
    (net (code "16") (name "Net-(D3-A)") (class "Default")
      (node (ref "BUZZER") (pin "2") (pinfunction "2_2") (pintype "unspecified"))
      (node (ref "D3") (pin "2") (pinfunction "A_2") (pintype "unspecified"))
      (node (ref "Q6") (pin "3") (pinfunction "C_3") (pintype "input"))
    )
    (net (code "17") (name "Net-(LED1-DOUT)") (class "Default")
      (node (ref "LED1") (pin "2") (pinfunction "DOUT_2") (pintype "unspecified"))
      (node (ref "LED2") (pin "4") (pinfunction "DIN_4") (pintype "unspecified"))
    )
    (net (code "18") (name "Net-(LED2-DOUT)") (class "Default")
      (node (ref "LED2") (pin "2") (pinfunction "DOUT_2") (pintype "unspecified"))
      (node (ref "LED3") (pin "4") (pinfunction "DIN_4") (pintype "unspecified"))
    )
    (net (code "19") (name "Net-(LED3-DOUT)") (class "Default")
      (node (ref "LED3") (pin "2") (pinfunction "DOUT_2") (pintype "unspecified"))
      (node (ref "LED4") (pin "4") (pinfunction "DIN_4") (pintype "unspecified"))
    )
    (net (code "20") (name "Net-(LED4-DOUT)") (class "Default")
      (node (ref "LED4") (pin "2") (pinfunction "DOUT_2") (pintype "unspecified"))
      (node (ref "LED5") (pin "4") (pinfunction "DIN_4") (pintype "unspecified"))
    )
    (net (code "21") (name "Net-(LED5-DOUT)") (class "Default")
      (node (ref "LED5") (pin "2") (pinfunction "DOUT_2") (pintype "unspecified"))
      (node (ref "LED6") (pin "4") (pinfunction "DIN_4") (pintype "unspecified"))
    )
    (net (code "22") (name "Net-(LED6-DOUT)") (class "Default")
      (node (ref "LED6") (pin "2") (pinfunction "DOUT_2") (pintype "unspecified"))
      (node (ref "LED7") (pin "4") (pinfunction "DIN_4") (pintype "unspecified"))
    )
    (net (code "23") (name "Net-(LED7-DOUT)") (class "Default")
      (node (ref "LED7") (pin "2") (pinfunction "DOUT_2") (pintype "unspecified"))
      (node (ref "LED8") (pin "4") (pinfunction "DIN_4") (pintype "unspecified"))
    )
    (net (code "24") (name "Net-(LED8-DOUT)") (class "Default")
      (node (ref "LED8") (pin "2") (pinfunction "DOUT_2") (pintype "unspecified"))
      (node (ref "LED9") (pin "4") (pinfunction "DIN_4") (pintype "unspecified"))
    )
    (net (code "25") (name "Net-(LED10-DIN)") (class "Default")
      (node (ref "LED10") (pin "4") (pinfunction "DIN_4") (pintype "unspecified"))
      (node (ref "LED9") (pin "2") (pinfunction "DOUT_2") (pintype "unspecified"))
    )
    (net (code "26") (name "Net-(Q1-G)") (class "Default")
      (node (ref "Q1") (pin "1") (pinfunction "G_1") (pintype "unspecified"))
      (node (ref "U2") (pin "40") (pinfunction "VBUS_40") (pintype "input"))
    )
    (net (code "27") (name "Net-(Q3-D)") (class "Default")
      (node (ref "CN1A") (pin "4") (pinfunction "4_4") (pintype "unspecified"))
      (node (ref "CN1B") (pin "4") (pinfunction "4_4") (pintype "unspecified"))
      (node (ref "Q3") (pin "3") (pinfunction "D_3") (pintype "unspecified"))
      (node (ref "R17") (pin "1") (pinfunction "1_1") (pintype "input"))
    )
    (net (code "28") (name "Net-(Q3-S)") (class "Default")
      (node (ref "Q3") (pin "2") (pinfunction "S_2") (pintype "unspecified"))
      (node (ref "R14") (pin "1") (pinfunction "1_1") (pintype "input"))
      (node (ref "U2") (pin "2") (pinfunction "GP1_2") (pintype "input"))
    )
    (net (code "29") (name "Net-(Q4-D)") (class "Default")
      (node (ref "CN1A") (pin "3") (pinfunction "3_3") (pintype "unspecified"))
      (node (ref "CN1B") (pin "3") (pinfunction "3_3") (pintype "unspecified"))
      (node (ref "Q4") (pin "3") (pinfunction "D_3") (pintype "unspecified"))
      (node (ref "R16") (pin "1") (pinfunction "1_1") (pintype "input"))
    )
    (net (code "30") (name "Net-(Q4-S)") (class "Default")
      (node (ref "Q4") (pin "2") (pinfunction "S_2") (pintype "unspecified"))
      (node (ref "R15") (pin "1") (pinfunction "1_1") (pintype "input"))
      (node (ref "U2") (pin "1") (pinfunction "GP0_1") (pintype "input"))
    )
    (net (code "31") (name "Net-(Q5-D)") (class "Default")
      (node (ref "Q5") (pin "3") (pinfunction "D_3") (pintype "unspecified"))
      (node (ref "R18") (pin "1") (pinfunction "1_1") (pintype "input"))
      (node (ref "SERVO") (pin "3") (pinfunction "3_3") (pintype "unspecified"))
    )
    (net (code "32") (name "Net-(Q5-S)") (class "Default")
      (node (ref "Q5") (pin "2") (pinfunction "S_2") (pintype "unspecified"))
      (node (ref "R19") (pin "1") (pinfunction "1_1") (pintype "input"))
      (node (ref "U2") (pin "9") (pinfunction "GP6_9") (pintype "input"))
    )
    (net (code "33") (name "Net-(Q6-B)") (class "Default")
      (node (ref "Q6") (pin "1") (pinfunction "B_1") (pintype "input"))
      (node (ref "R21") (pin "2") (pinfunction "2_2") (pintype "input"))
    )
    (net (code "34") (name "Net-(RESET-C)") (class "Default")
      (node (ref "RESET") (pin "3") (pinfunction "C_3") (pintype "unspecified"))
      (node (ref "U2") (pin "30") (pinfunction "RUN_30") (pintype "input"))
    )
    (net (code "35") (name "Net-(S1-B)") (class "Default")
      (node (ref "S1") (pin "2") (pinfunction "B_2") (pintype "unspecified"))
      (node (ref "U2") (pin "17") (pinfunction "GP13_17") (pintype "input"))
    )
    (net (code "36") (name "Net-(S2-B)") (class "Default")
      (node (ref "S2") (pin "2") (pinfunction "B_2") (pintype "unspecified"))
      (node (ref "U2") (pin "19") (pinfunction "GP14_19") (pintype "input"))
    )
    (net (code "37") (name "Net-(S3-B)") (class "Default")
      (node (ref "S3") (pin "2") (pinfunction "B_2") (pintype "unspecified"))
      (node (ref "U2") (pin "20") (pinfunction "GP15_20") (pintype "input"))
    )
    (net (code "38") (name "Net-(SW1-Anode)") (class "Default")
      (node (ref "R3") (pin "2") (pinfunction "2_2") (pintype "input"))
      (node (ref "SW1") (pin "4") (pinfunction "Anode_4") (pintype "unspecified"))
    )
    (net (code "39") (name "Net-(SW1-Collector)") (class "Default")
      (node (ref "R6") (pin "2") (pinfunction "2_2") (pintype "input"))
      (node (ref "SW1") (pin "2") (pinfunction "Collector_2") (pintype "unspecified"))
      (node (ref "U2") (pin "34") (pinfunction "GP28_34") (pintype "input"))
    )
    (net (code "40") (name "Net-(SW2-Anode)") (class "Default")
      (node (ref "R4") (pin "2") (pinfunction "2_2") (pintype "input"))
      (node (ref "SW2") (pin "4") (pinfunction "Anode_4") (pintype "unspecified"))
    )
    (net (code "41") (name "Net-(SW2-Collector)") (class "Default")
      (node (ref "R7") (pin "2") (pinfunction "2_2") (pintype "input"))
      (node (ref "SW2") (pin "2") (pinfunction "Collector_2") (pintype "unspecified"))
      (node (ref "U2") (pin "32") (pinfunction "GP27_32") (pintype "input"))
    )
    (net (code "42") (name "Net-(SW3-Anode)") (class "Default")
      (node (ref "R5") (pin "2") (pinfunction "2_2") (pintype "input"))
      (node (ref "SW3") (pin "4") (pinfunction "Anode_4") (pintype "unspecified"))
    )
    (net (code "43") (name "Net-(SW3-Collector)") (class "Default")
      (node (ref "R8") (pin "1") (pinfunction "1_1") (pintype "input"))
      (node (ref "SW3") (pin "2") (pinfunction "Collector_2") (pintype "unspecified"))
      (node (ref "U2") (pin "31") (pinfunction "GP26_31") (pintype "input"))
    )
    (net (code "44") (name "Net-(U1-EN)") (class "Default")
      (node (ref "C3") (pin "2") (pinfunction "2_2") (pintype "unspecified"))
      (node (ref "C4") (pin "2") (pinfunction "2_2") (pintype "unspecified"))
      (node (ref "U1") (pin "3") (pinfunction "VIN_3") (pintype "unspecified"))
      (node (ref "U1") (pin "5") (pinfunction "EN_5") (pintype "unspecified"))
      (node (ref "U10") (pin "3") (pinfunction "K_3") (pintype "unspecified"))
    )
    (net (code "45") (name "Net-(U1-SW)") (class "Default")
      (node (ref "C5") (pin "2") (pinfunction "2_2") (pintype "unspecified"))
      (node (ref "L1") (pin "1") (pinfunction "1_1") (pintype "unspecified"))
      (node (ref "U1") (pin "2") (pinfunction "SW_2") (pintype "unspecified"))
    )
    (net (code "46") (name "Net-(U1-VBST)") (class "Default")
      (node (ref "C5") (pin "1") (pinfunction "1_1") (pintype "unspecified"))
      (node (ref "U1") (pin "6") (pinfunction "VBST_6") (pintype "unspecified"))
    )
    (net (code "47") (name "Net-(U1-VFB)") (class "Default")
      (node (ref "R1") (pin "1") (pinfunction "1_1") (pintype "input"))
      (node (ref "R2") (pin "2") (pinfunction "2_2") (pintype "input"))
      (node (ref "U1") (pin "4") (pinfunction "VFB_4") (pintype "unspecified"))
    )
    (net (code "48") (name "Net-(U2-GP2)") (class "Default")
      (node (ref "CN2") (pin "3") (pinfunction "3_3") (pintype "unspecified"))
      (node (ref "U2") (pin "4") (pinfunction "GP2_4") (pintype "input"))
    )
    (net (code "49") (name "Net-(U2-GP3)") (class "Default")
      (node (ref "CN2") (pin "4") (pinfunction "4_4") (pintype "unspecified"))
      (node (ref "U2") (pin "5") (pinfunction "GP3_5") (pintype "input"))
    )
    (net (code "50") (name "Net-(U2-GP4)") (class "Default")
      (node (ref "CN3A") (pin "3") (pinfunction "3_3") (pintype "unspecified"))
      (node (ref "CN3B") (pin "3") (pinfunction "3_3") (pintype "unspecified"))
      (node (ref "U2") (pin "6") (pinfunction "GP4_6") (pintype "input"))
    )
    (net (code "51") (name "Net-(U2-GP5)") (class "Default")
      (node (ref "CN3A") (pin "4") (pinfunction "4_4") (pintype "unspecified"))
      (node (ref "CN3B") (pin "4") (pinfunction "4_4") (pintype "unspecified"))
      (node (ref "U2") (pin "7") (pinfunction "GP5_7") (pintype "input"))
    )
    (net (code "52") (name "Net-(U2-GP10)") (class "Default")
      (node (ref "R12") (pin "2") (pinfunction "2_2") (pintype "input"))
      (node (ref "U2") (pin "14") (pinfunction "GP10_14") (pintype "input"))
    )
    (net (code "53") (name "Net-(U2-GP11)") (class "Default")
      (node (ref "R13") (pin "2") (pinfunction "2_2") (pintype "input"))
      (node (ref "U2") (pin "15") (pinfunction "GP11_15") (pintype "input"))
    )
    (net (code "54") (name "Net-(U2-GP12)") (class "Default")
      (node (ref "U2") (pin "16") (pinfunction "GP12_16") (pintype "input"))
      (node (ref "U6") (pin "2") (pinfunction "A_2") (pintype "unspecified"))
    )
    (net (code "55") (name "Net-(U2-GP16)") (class "Default")
      (node (ref "U2") (pin "21") (pinfunction "GP16_21") (pintype "input"))
      (node (ref "U3") (pin "8") (pinfunction "DIR_8") (pintype "unspecified"))
    )
    (net (code "56") (name "Net-(U2-GP17)") (class "Default")
      (node (ref "U2") (pin "22") (pinfunction "GP17_22") (pintype "input"))
      (node (ref "U3") (pin "7") (pinfunction "STEP_7") (pintype "unspecified"))
    )
    (net (code "57") (name "Net-(U2-GP18)") (class "Default")
      (node (ref "U2") (pin "24") (pinfunction "GP18_24") (pintype "input"))
      (node (ref "U3") (pin "6") (pinfunction "SLP#_6") (pintype "unspecified"))
    )
    (net (code "58") (name "Net-(U2-GP19)") (class "Default")
      (node (ref "U2") (pin "25") (pinfunction "GP19_25") (pintype "input"))
      (node (ref "U4") (pin "8") (pinfunction "DIR_8") (pintype "unspecified"))
    )
    (net (code "59") (name "Net-(U2-GP20)") (class "Default")
      (node (ref "U2") (pin "26") (pinfunction "GP20_26") (pintype "input"))
      (node (ref "U4") (pin "7") (pinfunction "STEP_7") (pintype "unspecified"))
    )
    (net (code "60") (name "Net-(U2-GP21)") (class "Default")
      (node (ref "U2") (pin "27") (pinfunction "GP21_27") (pintype "input"))
      (node (ref "U4") (pin "6") (pinfunction "SLP#_6") (pintype "unspecified"))
    )
    (net (code "61") (name "Net-(U3-1A)") (class "Default")
      (node (ref "H4") (pin "3") (pinfunction "3_3") (pintype "unspecified"))
      (node (ref "U3") (pin "12") (pinfunction "1A_12") (pintype "unspecified"))
    )
    (net (code "62") (name "Net-(U3-1B)") (class "Default")
      (node (ref "H4") (pin "4") (pinfunction "4_4") (pintype "unspecified"))
      (node (ref "U3") (pin "11") (pinfunction "1B_11") (pintype "unspecified"))
    )
    (net (code "63") (name "Net-(U3-2A)") (class "Default")
      (node (ref "H4") (pin "2") (pinfunction "2_2") (pintype "unspecified"))
      (node (ref "U3") (pin "13") (pinfunction "2A_13") (pintype "unspecified"))
    )
    (net (code "64") (name "Net-(U3-2B)") (class "Default")
      (node (ref "H4") (pin "1") (pinfunction "1_1") (pintype "unspecified"))
      (node (ref "U3") (pin "14") (pinfunction "2B_14") (pintype "unspecified"))
    )
    (net (code "65") (name "Net-(U4-1A)") (class "Default")
      (node (ref "H3") (pin "3") (pinfunction "3_3") (pintype "unspecified"))
      (node (ref "U4") (pin "12") (pinfunction "1A_12") (pintype "unspecified"))
    )
    (net (code "66") (name "Net-(U4-1B)") (class "Default")
      (node (ref "H3") (pin "4") (pinfunction "4_4") (pintype "unspecified"))
      (node (ref "U4") (pin "11") (pinfunction "1B_11") (pintype "unspecified"))
    )
    (net (code "67") (name "Net-(U4-2A)") (class "Default")
      (node (ref "H3") (pin "2") (pinfunction "2_2") (pintype "unspecified"))
      (node (ref "U4") (pin "13") (pinfunction "2A_13") (pintype "unspecified"))
    )
    (net (code "68") (name "Net-(U4-2B)") (class "Default")
      (node (ref "H3") (pin "1") (pinfunction "1_1") (pintype "unspecified"))
      (node (ref "U4") (pin "14") (pinfunction "2B_14") (pintype "unspecified"))
    )
    (net (code "69") (name "Net-(U5-K)") (class "Default")
      (node (ref "R9") (pin "1") (pinfunction "1_1") (pintype "input"))
      (node (ref "U5") (pin "1") (pinfunction "K_1") (pintype "unspecified"))
    )
    (net (code "70") (name "Net-(U6-K)") (class "Default")
      (node (ref "R10") (pin "2") (pinfunction "2_2") (pintype "input"))
      (node (ref "U6") (pin "1") (pinfunction "K_1") (pintype "unspecified"))
    )
    (net (code "71") (name "RGB") (class "Default")
      (node (ref "LED1") (pin "4") (pinfunction "DIN_4") (pintype "unspecified"))
      (node (ref "U2") (pin "29") (pinfunction "GP22_29") (pintype "input"))
    )
    (net (code "72") (name "UIN") (class "Default")
      (node (ref "C10") (pin "1") (pinfunction "1_1") (pintype "input"))
      (node (ref "C11") (pin "1") (pinfunction "1_1") (pintype "input"))
      (node (ref "C12") (pin "1") (pinfunction "1_1") (pintype "input"))
      (node (ref "C13") (pin "1") (pinfunction "1_1") (pintype "input"))
      (node (ref "D1") (pin "1") (pinfunction "1_1") (pintype "unspecified"))
      (node (ref "D2") (pin "2") (pinfunction "2_2") (pintype "unspecified"))
      (node (ref "U3") (pin "16") (pinfunction "VMOT_16") (pintype "unspecified"))
      (node (ref "U4") (pin "16") (pinfunction "VMOT_16") (pintype "unspecified"))
      (node (ref "U9") (pin "3") (pinfunction "K_3") (pintype "unspecified"))
    )
    (net (code "73") (name "unconnected-(6050-AUX_CL-Pad7)") (class "Default")
      (node (ref "6050") (pin "7") (pinfunction "AUX_CL_7") (pintype "unspecified+no_connect"))
    )
    (net (code "74") (name "unconnected-(6050-AUX_DA-Pad6)") (class "Default")
      (node (ref "6050") (pin "6") (pinfunction "AUX_DA_6") (pintype "unspecified+no_connect"))
    )
    (net (code "75") (name "unconnected-(6050-EP-Pad25)") (class "Default")
      (node (ref "6050") (pin "25") (pinfunction "EP_25") (pintype "unspecified+no_connect"))
    )
    (net (code "76") (name "unconnected-(6050-NC-Pad2)") (class "Default")
      (node (ref "6050") (pin "2") (pinfunction "NC_2") (pintype "unspecified+no_connect"))
    )
    (net (code "77") (name "unconnected-(6050-NC-Pad3)") (class "Default")
      (node (ref "6050") (pin "3") (pinfunction "NC_3") (pintype "unspecified+no_connect"))
    )
    (net (code "78") (name "unconnected-(6050-NC-Pad4)") (class "Default")
      (node (ref "6050") (pin "4") (pinfunction "NC_4") (pintype "unspecified+no_connect"))
    )
    (net (code "79") (name "unconnected-(6050-NC-Pad5)") (class "Default")
      (node (ref "6050") (pin "5") (pinfunction "NC_5") (pintype "unspecified+no_connect"))
    )
    (net (code "80") (name "unconnected-(6050-NC-Pad14)") (class "Default")
      (node (ref "6050") (pin "14") (pinfunction "NC_14") (pintype "unspecified+no_connect"))
    )
    (net (code "81") (name "unconnected-(6050-NC-Pad15)") (class "Default")
      (node (ref "6050") (pin "15") (pinfunction "NC_15") (pintype "unspecified+no_connect"))
    )
    (net (code "82") (name "unconnected-(6050-NC-Pad16)") (class "Default")
      (node (ref "6050") (pin "16") (pinfunction "NC_16") (pintype "unspecified+no_connect"))
    )
    (net (code "83") (name "unconnected-(6050-NC-Pad17)") (class "Default")
      (node (ref "6050") (pin "17") (pinfunction "NC_17") (pintype "unspecified+no_connect"))
    )
    (net (code "84") (name "unconnected-(6050-RESV-Pad19)") (class "Default")
      (node (ref "6050") (pin "19") (pinfunction "RESV_19") (pintype "unspecified+no_connect"))
    )
    (net (code "85") (name "unconnected-(6050-RESV-Pad21)") (class "Default")
      (node (ref "6050") (pin "21") (pinfunction "RESV_21") (pintype "unspecified+no_connect"))
    )
    (net (code "86") (name "unconnected-(6050-RESV-Pad22)") (class "Default")
      (node (ref "6050") (pin "22") (pinfunction "RESV_22") (pintype "unspecified+no_connect"))
    )
    (net (code "87") (name "unconnected-(BUZZER-Pad3)") (class "Default")
      (node (ref "BUZZER") (pin "3") (pinfunction "3_3") (pintype "unspecified+no_connect"))
    )
    (net (code "88") (name "unconnected-(BUZZER-Pad4)") (class "Default")
      (node (ref "BUZZER") (pin "4") (pinfunction "4_4") (pintype "unspecified+no_connect"))
    )
    (net (code "89") (name "unconnected-(CN1A-Pad0)") (class "Default")
      (node (ref "CN1A") (pin "0") (pinfunction "0_0") (pintype "unspecified+no_connect"))
    )
    (net (code "90") (name "unconnected-(CN1B-Pad0)") (class "Default")
      (node (ref "CN1B") (pin "0") (pinfunction "0_0") (pintype "unspecified+no_connect"))
    )
    (net (code "91") (name "unconnected-(CN2-Pad0)") (class "Default")
      (node (ref "CN2") (pin "0") (pinfunction "0_0") (pintype "unspecified+no_connect"))
    )
    (net (code "92") (name "unconnected-(CN3A-Pad0)") (class "Default")
      (node (ref "CN3A") (pin "0") (pinfunction "0_0") (pintype "unspecified+no_connect"))
    )
    (net (code "93") (name "unconnected-(CN3B-Pad0)") (class "Default")
      (node (ref "CN3B") (pin "0") (pinfunction "0_0") (pintype "unspecified+no_connect"))
    )
    (net (code "94") (name "unconnected-(LED10-DOUT-Pad2)") (class "Default")
      (node (ref "LED10") (pin "2") (pinfunction "DOUT_2") (pintype "unspecified+no_connect"))
    )
    (net (code "95") (name "unconnected-(RESET-A-Pad1)") (class "Default")
      (node (ref "RESET") (pin "1") (pinfunction "A_1") (pintype "unspecified+no_connect"))
    )
    (net (code "96") (name "unconnected-(RESET-D-Pad4)") (class "Default")
      (node (ref "RESET") (pin "4") (pinfunction "D_4") (pintype "unspecified+no_connect"))
    )
    (net (code "97") (name "unconnected-(S1-A-Pad1)") (class "Default")
      (node (ref "S1") (pin "1") (pinfunction "A_1") (pintype "unspecified+no_connect"))
    )
    (net (code "98") (name "unconnected-(S1-D-Pad4)") (class "Default")
      (node (ref "S1") (pin "4") (pinfunction "D_4") (pintype "unspecified+no_connect"))
    )
    (net (code "99") (name "unconnected-(S2-A-Pad1)") (class "Default")
      (node (ref "S2") (pin "1") (pinfunction "A_1") (pintype "unspecified+no_connect"))
    )
    (net (code "100") (name "unconnected-(S2-D-Pad4)") (class "Default")
      (node (ref "S2") (pin "4") (pinfunction "D_4") (pintype "unspecified+no_connect"))
    )
    (net (code "101") (name "unconnected-(S3-A-Pad1)") (class "Default")
      (node (ref "S3") (pin "1") (pinfunction "A_1") (pintype "unspecified+no_connect"))
    )
    (net (code "102") (name "unconnected-(S3-D-Pad4)") (class "Default")
      (node (ref "S3") (pin "4") (pinfunction "D_4") (pintype "unspecified+no_connect"))
    )
    (net (code "103") (name "unconnected-(U2-3V3_EN-Pad37)") (class "Default")
      (node (ref "U2") (pin "37") (pinfunction "3V3_EN_37") (pintype "input+no_connect"))
    )
    (net (code "104") (name "unconnected-(U3-EN#-Pad1)") (class "Default")
      (node (ref "U3") (pin "1") (pinfunction "EN#_1") (pintype "unspecified+no_connect"))
    )
    (net (code "105") (name "unconnected-(U3-VDD-Pad10)") (class "Default")
      (node (ref "U3") (pin "10") (pinfunction "VDD_10") (pintype "unspecified+no_connect"))
    )
    (net (code "106") (name "unconnected-(U4-EN#-Pad1)") (class "Default")
      (node (ref "U4") (pin "1") (pinfunction "EN#_1") (pintype "unspecified+no_connect"))
    )
    (net (code "107") (name "unconnected-(U4-VDD-Pad10)") (class "Default")
      (node (ref "U4") (pin "10") (pinfunction "VDD_10") (pintype "unspecified+no_connect"))
    )
  )
)
